# LinTempCont_indCh_V1_0.net
KiCad netlist of a schematic drawn in EAGLE
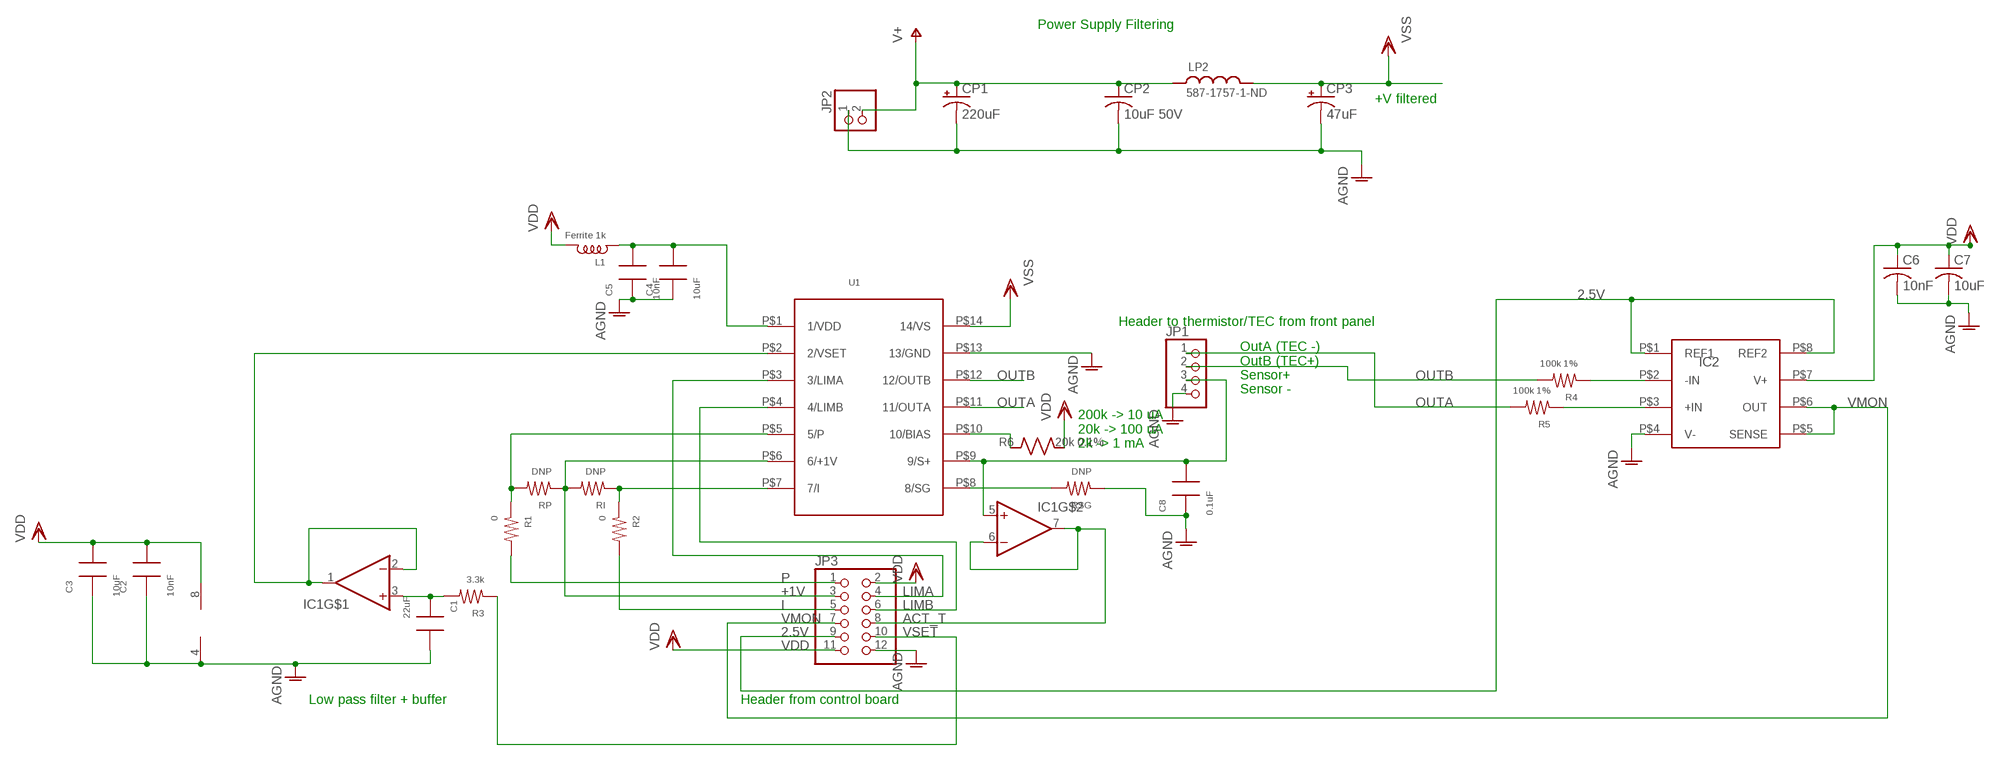
[diagram p0: schematic, sheet 1]

(export (version "E")
  (design (tool "Eeschema 10.0.6"))
  (components
    (comp (ref "C1")
      (value "22uF")
      (footprint "eagle-import:0805")
      (libsource (lib "eagle-import") (part "CAP0805"))
    )
    (comp (ref "C2")
      (value "10nF")
      (footprint "eagle-import:0603")
      (libsource (lib "eagle-import") (part "CAP0603"))
    )
    (comp (ref "C3")
      (value "10uF")
      (footprint "eagle-import:0805")
      (libsource (lib "eagle-import") (part "CAP0805"))
    )
    (comp (ref "C4")
      (value "10uF")
      (footprint "eagle-import:0805")
      (libsource (lib "eagle-import") (part "CAP0805"))
    )
    (comp (ref "C5")
      (value "10nF")
      (footprint "eagle-import:0603")
      (libsource (lib "eagle-import") (part "CAP0603"))
    )
    (comp (ref "C6")
      (value "10nF")
      (footprint "eagle-import:C0603")
      (libsource (lib "eagle-import") (part "C-USC0603"))
    )
    (comp (ref "C7")
      (value "10uF")
      (footprint "eagle-import:C0805")
      (libsource (lib "eagle-import") (part "C-USC0805"))
    )
    (comp (ref "C8")
      (value "0.1uF")
      (footprint "eagle-import:0603")
      (libsource (lib "eagle-import") (part "CAP0603"))
    )
    (comp (ref "CP1")
      (value "220uF")
      (footprint "eagle-import:PANASONIC_F")
      (libsource (lib "eagle-import") (part "CPOL-USF"))
    )
    (comp (ref "CP2")
      (value "10uF 50V")
      (footprint "eagle-import:C1206")
      (libsource (lib "eagle-import") (part "C-USC1206"))
    )
    (comp (ref "CP3")
      (value "47uF")
      (footprint "eagle-import:CT7343")
      (libsource (lib "eagle-import") (part "CPOL-USCT7343"))
    )
    (comp (ref "IC1")
      (value "OP727")
      (footprint "eagle-import:TSSOP8")
      (libsource (lib "eagle-import") (part "OP727"))
    )
    (comp (ref "IC2")
      (value "INA159")
      (footprint "eagle-import:VSSOP8")
      (libsource (lib "eagle-import") (part "INA159"))
    )
    (comp (ref "JP1")
      (value "SCRWTRM-1X4/90_ED550")
      (footprint "eagle-import:1X04_RA_SCRWTRM_ED550")
      (libsource (lib "eagle-import") (part "SCRWTRM-1X4/90_ED550"))
    )
    (comp (ref "JP2")
      (value "SCRWTRM-1X2/90_ED550")
      (footprint "eagle-import:1X02_RA_SCRWTRM_ED550")
      (libsource (lib "eagle-import") (part "SCRWTRM-1X2/90_ED550"))
    )
    (comp (ref "JP3")
      (value "PINHD-2X6")
      (footprint "eagle-import:2X06")
      (libsource (lib "eagle-import") (part "PINHD-2X6"))
    )
    (comp (ref "L1")
      (value "Ferrite 1k")
      (footprint "eagle-import:0805")
      (libsource (lib "eagle-import") (part "INDUCTOR-0805"))
    )
    (comp (ref "LP2")
      (value "587-1757-1-ND")
      (footprint "eagle-import:L_FERRITE_1810")
      (libsource (lib "eagle-import") (part "L_FERRITE_SMD"))
    )
    (comp (ref "R1")
      (value "0")
      (footprint "eagle-import:0603")
      (libsource (lib "eagle-import") (part "RES0603"))
    )
    (comp (ref "R2")
      (value "0")
      (footprint "eagle-import:0603")
      (libsource (lib "eagle-import") (part "RES0603"))
    )
    (comp (ref "R3")
      (value "3.3k")
      (footprint "eagle-import:0603")
      (libsource (lib "eagle-import") (part "RES0603"))
    )
    (comp (ref "R4")
      (value "100k 1%")
      (footprint "eagle-import:0603")
      (libsource (lib "eagle-import") (part "RES0603"))
    )
    (comp (ref "R5")
      (value "100k 1%")
      (footprint "eagle-import:0603")
      (libsource (lib "eagle-import") (part "RES0603"))
    )
    (comp (ref "R6")
      (value "20k 0.1%")
      (footprint "eagle-import:R_0805")
      (libsource (lib "eagle-import") (part "R_SMDR0805"))
    )
    (comp (ref "RI")
      (value "DNP")
      (footprint "eagle-import:0603")
      (libsource (lib "eagle-import") (part "RES0603"))
    )
    (comp (ref "RP")
      (value "DNP")
      (footprint "eagle-import:0603")
      (libsource (lib "eagle-import") (part "RES0603"))
    )
    (comp (ref "RSG")
      (value "DNP")
      (footprint "eagle-import:0603")
      (libsource (lib "eagle-import") (part "RES0603"))
    )
    (comp (ref "U1")
      (value "WTC3243")
      (footprint "eagle-import:WTC3293")
      (libsource (lib "eagle-import") (part "WTC3243"))
    )
  )
  (nets
    (net (code "1") (name "/+1V") (class "Default")
      (node (ref "JP3") (pin "3") (pinfunction "3_3") (pintype "passive"))
      (node (ref "RI") (pin "2") (pinfunction "P$2_2") (pintype "passive"))
      (node (ref "RP") (pin "1") (pinfunction "P$1_1") (pintype "passive"))
      (node (ref "U1") (pin "P$6") (pinfunction "6/+1V_P$6") (pintype "bidirectional"))
    )
    (net (code "2") (name "/2.5V") (class "Default")
      (node (ref "IC2") (pin "P$1") (pinfunction "REF1_P$1") (pintype "bidirectional"))
      (node (ref "IC2") (pin "P$8") (pinfunction "REF2_P$8") (pintype "bidirectional"))
      (node (ref "JP3") (pin "9") (pinfunction "9_9") (pintype "passive"))
    )
    (net (code "3") (name "/ACT_T") (class "Default")
      (node (ref "IC1") (pin "6") (pinfunction "-IN_6") (pintype "input"))
      (node (ref "IC1") (pin "7") (pinfunction "OUT_7") (pintype "output"))
      (node (ref "JP3") (pin "8") (pinfunction "8_8") (pintype "passive"))
    )
    (net (code "4") (name "/I") (class "Default")
      (node (ref "JP3") (pin "5") (pinfunction "5_5") (pintype "passive"))
      (node (ref "R2") (pin "2") (pinfunction "P$2_2") (pintype "passive"))
    )
    (net (code "5") (name "/LIMA") (class "Default")
      (node (ref "JP3") (pin "4") (pinfunction "4_4") (pintype "passive"))
      (node (ref "U1") (pin "P$3") (pinfunction "3/LIMA_P$3") (pintype "bidirectional"))
    )
    (net (code "6") (name "/LIMB") (class "Default")
      (node (ref "JP3") (pin "6") (pinfunction "6_6") (pintype "passive"))
      (node (ref "U1") (pin "P$4") (pinfunction "4/LIMB_P$4") (pintype "bidirectional"))
    )
    (net (code "7") (name "/OUTA") (class "Default")
      (node (ref "JP1") (pin "1") (pinfunction "1_1") (pintype "passive"))
      (node (ref "R5") (pin "2") (pinfunction "P$2_2") (pintype "passive"))
      (node (ref "U1") (pin "P$11") (pinfunction "11/OUTA_P$11") (pintype "bidirectional"))
    )
    (net (code "8") (name "/OUTB") (class "Default")
      (node (ref "JP1") (pin "2") (pinfunction "2_2") (pintype "passive"))
      (node (ref "R4") (pin "2") (pinfunction "P$2_2") (pintype "passive"))
      (node (ref "U1") (pin "P$12") (pinfunction "12/OUTB_P$12") (pintype "bidirectional"))
    )
    (net (code "9") (name "/P") (class "Default")
      (node (ref "JP3") (pin "1") (pinfunction "1_1") (pintype "passive"))
      (node (ref "R1") (pin "2") (pinfunction "P$2_2") (pintype "passive"))
    )
    (net (code "10") (name "/VMON") (class "Default")
      (node (ref "IC2") (pin "P$5") (pinfunction "SENSE_P$5") (pintype "bidirectional"))
      (node (ref "IC2") (pin "P$6") (pinfunction "OUT_P$6") (pintype "bidirectional"))
      (node (ref "JP3") (pin "7") (pinfunction "7_7") (pintype "passive"))
    )
    (net (code "11") (name "/VSET") (class "Default")
      (node (ref "JP3") (pin "10") (pinfunction "10_10") (pintype "passive"))
      (node (ref "R3") (pin "1") (pinfunction "P$1_1") (pintype "passive"))
    )
    (net (code "12") (name "AGND") (class "Default")
      (node (ref "C1") (pin "2") (pinfunction "P$2_2") (pintype "passive"))
      (node (ref "C2") (pin "1") (pinfunction "P$1_1") (pintype "passive"))
      (node (ref "C3") (pin "1") (pinfunction "P$1_1") (pintype "passive"))
      (node (ref "C4") (pin "1") (pinfunction "P$1_1") (pintype "passive"))
      (node (ref "C5") (pin "1") (pinfunction "P$1_1") (pintype "passive"))
      (node (ref "C6") (pin "2") (pinfunction "2_2") (pintype "passive"))
      (node (ref "C7") (pin "2") (pinfunction "2_2") (pintype "passive"))
      (node (ref "C8") (pin "1") (pinfunction "P$1_1") (pintype "passive"))
      (node (ref "CP1") (pin "-") (pinfunction "-_-") (pintype "passive"))
      (node (ref "CP2") (pin "2") (pinfunction "2_2") (pintype "passive"))
      (node (ref "CP3") (pin "-") (pinfunction "-_-") (pintype "passive"))
      (node (ref "IC1") (pin "4") (pinfunction "V-_4") (pintype "power_in"))
      (node (ref "IC2") (pin "P$4") (pinfunction "V-_P$4") (pintype "power_in"))
      (node (ref "JP1") (pin "4") (pinfunction "4_4") (pintype "passive"))
      (node (ref "JP2") (pin "1") (pinfunction "1_1") (pintype "passive"))
      (node (ref "JP3") (pin "12") (pinfunction "12_12") (pintype "passive"))
      (node (ref "RSG") (pin "1") (pinfunction "P$1_1") (pintype "passive"))
      (node (ref "U1") (pin "P$13") (pinfunction "13/GND_P$13") (pintype "power_in"))
    )
    (net (code "13") (name "Net-(C1-P$1)") (class "Default")
      (node (ref "C1") (pin "1") (pinfunction "P$1_1") (pintype "passive"))
      (node (ref "IC1") (pin "3") (pinfunction "+IN_3") (pintype "input"))
      (node (ref "R3") (pin "2") (pinfunction "P$2_2") (pintype "passive"))
    )
    (net (code "14") (name "Net-(C4-P$2)") (class "Default")
      (node (ref "C4") (pin "2") (pinfunction "P$2_2") (pintype "passive"))
      (node (ref "C5") (pin "2") (pinfunction "P$2_2") (pintype "passive"))
      (node (ref "L1") (pin "1") (pinfunction "P$1_1") (pintype "passive"))
      (node (ref "U1") (pin "P$1") (pinfunction "1/VDD_P$1") (pintype "power_in"))
    )
    (net (code "15") (name "Net-(C8-P$2)") (class "Default")
      (node (ref "C8") (pin "2") (pinfunction "P$2_2") (pintype "passive"))
      (node (ref "IC1") (pin "5") (pinfunction "+IN_5") (pintype "input"))
      (node (ref "JP1") (pin "3") (pinfunction "3_3") (pintype "passive"))
      (node (ref "U1") (pin "P$9") (pinfunction "9/S+_P$9") (pintype "bidirectional"))
    )
    (net (code "16") (name "Net-(IC1A--IN)") (class "Default")
      (node (ref "IC1") (pin "1") (pinfunction "OUT_1") (pintype "output"))
      (node (ref "IC1") (pin "2") (pinfunction "-IN_2") (pintype "input"))
      (node (ref "U1") (pin "P$2") (pinfunction "2/VSET_P$2") (pintype "input"))
    )
    (net (code "17") (name "Net-(IC2-+IN)") (class "Default")
      (node (ref "IC2") (pin "P$3") (pinfunction "+IN_P$3") (pintype "bidirectional"))
      (node (ref "R5") (pin "1") (pinfunction "P$1_1") (pintype "passive"))
    )
    (net (code "18") (name "Net-(IC2--IN)") (class "Default")
      (node (ref "IC2") (pin "P$2") (pinfunction "-IN_P$2") (pintype "bidirectional"))
      (node (ref "R4") (pin "1") (pinfunction "P$1_1") (pintype "passive"))
    )
    (net (code "19") (name "Net-(R1-P$1)") (class "Default")
      (node (ref "R1") (pin "1") (pinfunction "P$1_1") (pintype "passive"))
      (node (ref "RP") (pin "2") (pinfunction "P$2_2") (pintype "passive"))
      (node (ref "U1") (pin "P$5") (pinfunction "5/P_P$5") (pintype "bidirectional"))
    )
    (net (code "20") (name "Net-(R2-P$1)") (class "Default")
      (node (ref "R2") (pin "1") (pinfunction "P$1_1") (pintype "passive"))
      (node (ref "RI") (pin "1") (pinfunction "P$1_1") (pintype "passive"))
      (node (ref "U1") (pin "P$7") (pinfunction "7/I_P$7") (pintype "bidirectional"))
    )
    (net (code "21") (name "Net-(R6-1)") (class "Default")
      (node (ref "R6") (pin "P$1") (pinfunction "1_P$1") (pintype "passive"))
      (node (ref "U1") (pin "P$10") (pinfunction "10/BIAS_P$10") (pintype "bidirectional"))
    )
    (net (code "22") (name "Net-(RSG-P$2)") (class "Default")
      (node (ref "RSG") (pin "2") (pinfunction "P$2_2") (pintype "passive"))
      (node (ref "U1") (pin "P$8") (pinfunction "8/SG_P$8") (pintype "bidirectional"))
    )
    (net (code "23") (name "V+") (class "Default")
      (node (ref "CP1") (pin "+") (pinfunction "+_+") (pintype "passive"))
      (node (ref "CP2") (pin "1") (pinfunction "1_1") (pintype "passive"))
      (node (ref "JP2") (pin "2") (pinfunction "2_2") (pintype "passive"))
      (node (ref "LP2") (pin "P$1") (pinfunction "1_P$1") (pintype "passive"))
    )
    (net (code "24") (name "VDD") (class "Default")
      (node (ref "C2") (pin "2") (pinfunction "P$2_2") (pintype "passive"))
      (node (ref "C3") (pin "2") (pinfunction "P$2_2") (pintype "passive"))
      (node (ref "C6") (pin "1") (pinfunction "1_1") (pintype "passive"))
      (node (ref "C7") (pin "1") (pinfunction "1_1") (pintype "passive"))
      (node (ref "IC1") (pin "8") (pinfunction "V+_8") (pintype "power_in"))
      (node (ref "IC2") (pin "P$7") (pinfunction "V+_P$7") (pintype "power_in"))
      (node (ref "JP3") (pin "11") (pinfunction "11_11") (pintype "passive"))
      (node (ref "JP3") (pin "2") (pinfunction "2_2") (pintype "passive"))
      (node (ref "L1") (pin "2") (pinfunction "P$2_2") (pintype "passive"))
      (node (ref "R6") (pin "P$2") (pinfunction "2_P$2") (pintype "passive"))
    )
    (net (code "25") (name "VSS") (class "Default")
      (node (ref "CP3") (pin "+") (pinfunction "+_+") (pintype "passive"))
      (node (ref "LP2") (pin "P$2") (pinfunction "2_P$2") (pintype "passive"))
      (node (ref "U1") (pin "P$14") (pinfunction "14/VS_P$14") (pintype "power_in"))
    )
  )
)
